# M661A.net
KiCad netlist of a schematic drawn in EAGLE
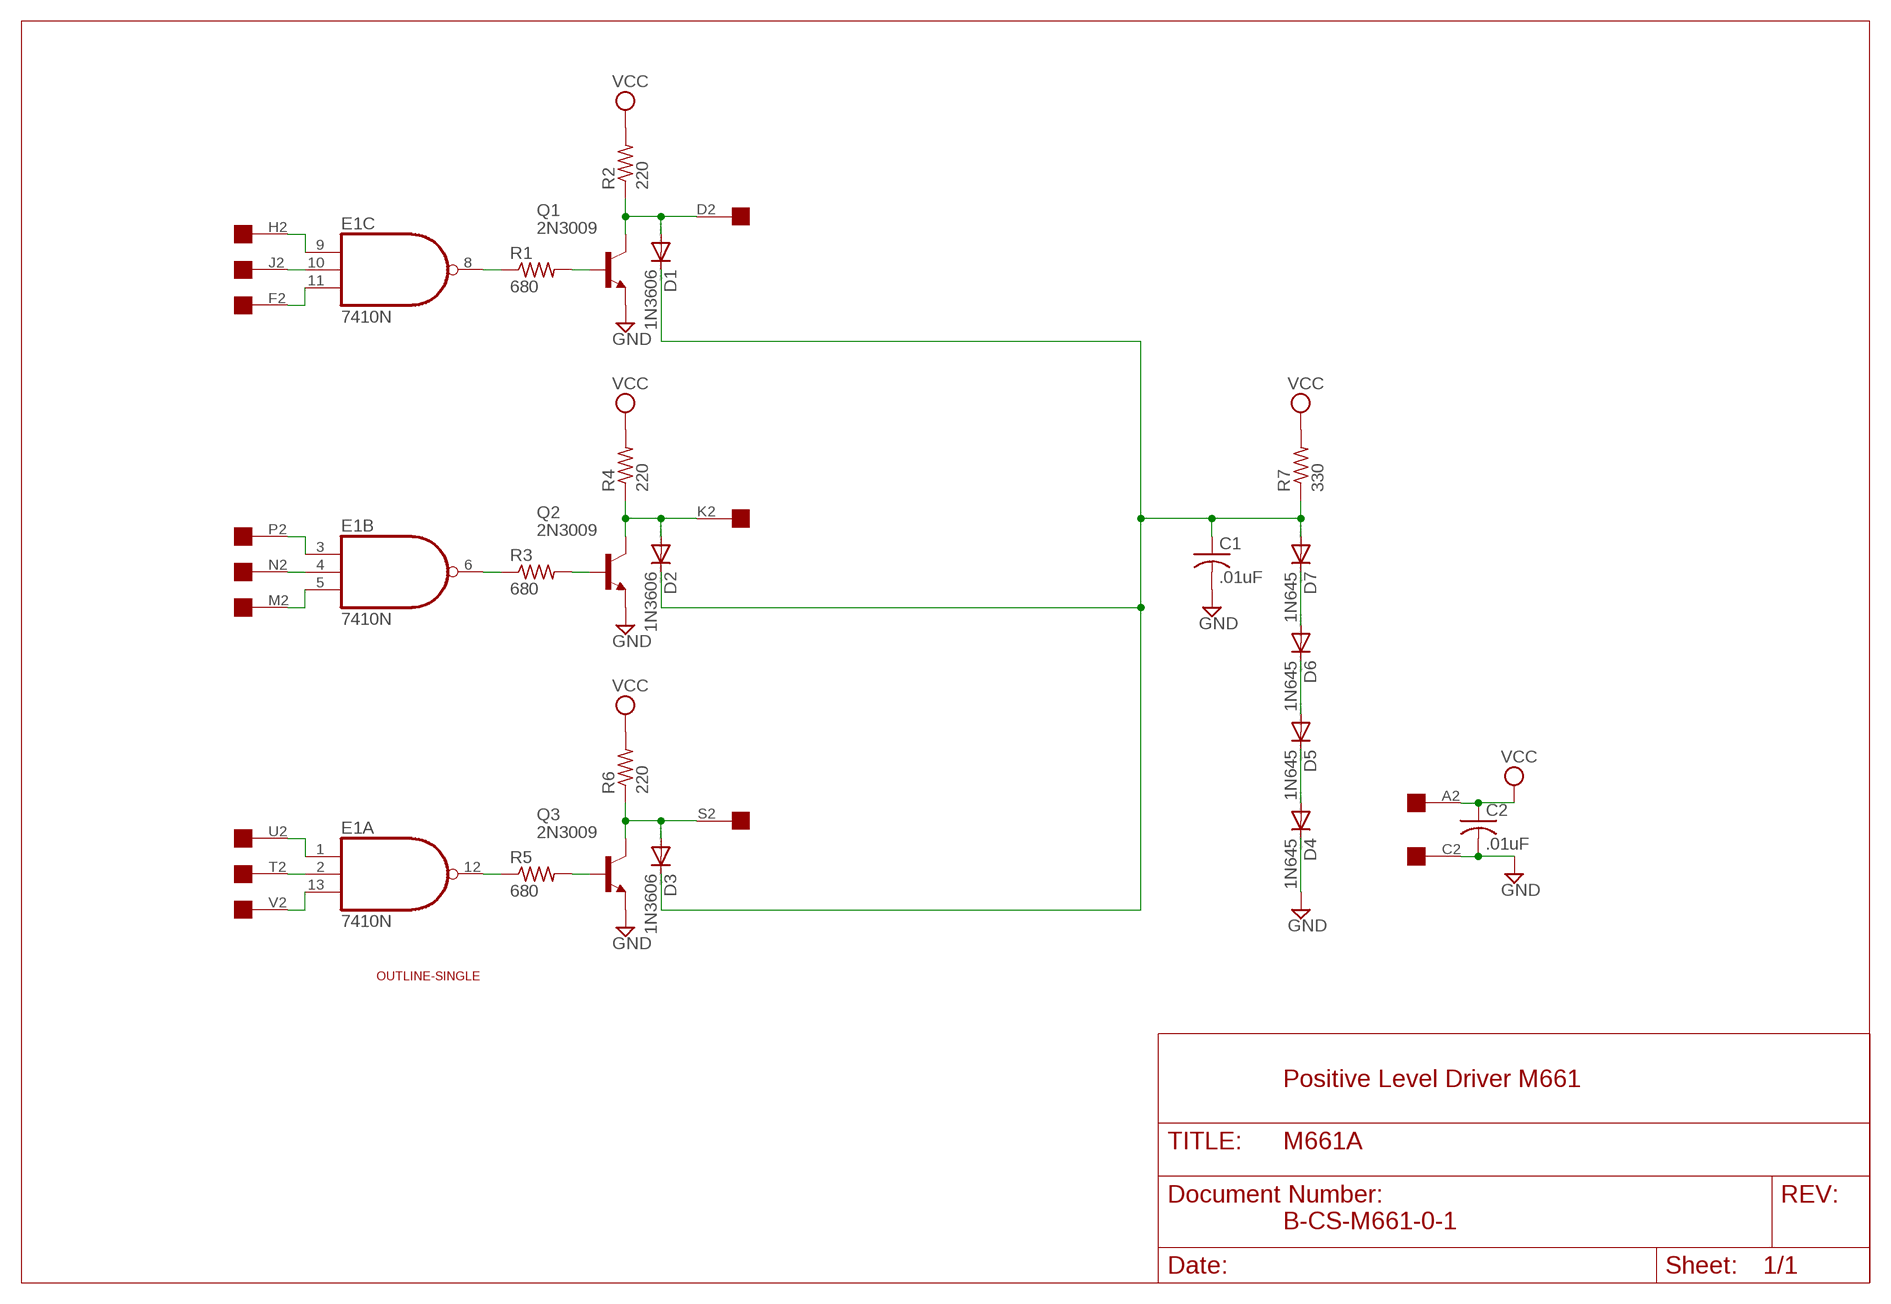
[diagram p0: schematic, sheet 1]

(export (version "E")
  (design (tool "Eeschema 10.0.6"))
  (components
    (comp (ref "C1")
      (value ".01uF")
      (footprint "eagle-import:C050-025X075")
      (libsource (lib "eagle-import") (part "C-US050-025X075"))
    )
    (comp (ref "C2")
      (value ".01uF")
      (footprint "eagle-import:C050-025X075")
      (libsource (lib "eagle-import") (part "C-US050-025X075"))
    )
    (comp (ref "D1")
      (value "1N3606")
      (footprint "eagle-import:DO35-10")
      (libsource (lib "eagle-import") (part "1N4148DO35-10"))
    )
    (comp (ref "D2")
      (value "1N3606")
      (footprint "eagle-import:DO35-10")
      (libsource (lib "eagle-import") (part "1N4148DO35-10"))
    )
    (comp (ref "D3")
      (value "1N3606")
      (footprint "eagle-import:DO35-10")
      (libsource (lib "eagle-import") (part "1N4148DO35-10"))
    )
    (comp (ref "D4")
      (value "1N645")
      (footprint "eagle-import:DO35-10")
      (libsource (lib "eagle-import") (part "1N4148DO35-10"))
    )
    (comp (ref "D5")
      (value "1N645")
      (footprint "eagle-import:DO35-10")
      (libsource (lib "eagle-import") (part "1N4148DO35-10"))
    )
    (comp (ref "D6")
      (value "1N645")
      (footprint "eagle-import:DO35-10")
      (libsource (lib "eagle-import") (part "1N4148DO35-10"))
    )
    (comp (ref "D7")
      (value "1N645")
      (footprint "eagle-import:DO35-10")
      (libsource (lib "eagle-import") (part "1N4148DO35-10"))
    )
    (comp (ref "E1")
      (value "7410N")
      (footprint "eagle-import:DIL14")
      (libsource (lib "eagle-import") (part "7410N"))
    )
    (comp (ref "Q1")
      (value "2N3009")
      (footprint "eagle-import:TO5")
      (libsource (lib "eagle-import") (part "2N2219"))
    )
    (comp (ref "Q2")
      (value "2N3009")
      (footprint "eagle-import:TO5")
      (libsource (lib "eagle-import") (part "2N2219"))
    )
    (comp (ref "Q3")
      (value "2N3009")
      (footprint "eagle-import:TO5")
      (libsource (lib "eagle-import") (part "2N2219"))
    )
    (comp (ref "R1")
      (value "680")
      (footprint "eagle-import:0207_10")
      (libsource (lib "eagle-import") (part "R-US_0207/10"))
    )
    (comp (ref "R2")
      (value "220")
      (footprint "eagle-import:0207_10")
      (libsource (lib "eagle-import") (part "R-US_0207/10"))
    )
    (comp (ref "R3")
      (value "680")
      (footprint "eagle-import:0207_10")
      (libsource (lib "eagle-import") (part "R-US_0207/10"))
    )
    (comp (ref "R4")
      (value "220")
      (footprint "eagle-import:0207_10")
      (libsource (lib "eagle-import") (part "R-US_0207/10"))
    )
    (comp (ref "R5")
      (value "680")
      (footprint "eagle-import:0207_10")
      (libsource (lib "eagle-import") (part "R-US_0207/10"))
    )
    (comp (ref "R6")
      (value "220")
      (footprint "eagle-import:0207_10")
      (libsource (lib "eagle-import") (part "R-US_0207/10"))
    )
    (comp (ref "R7")
      (value "330")
      (footprint "eagle-import:0207_10")
      (libsource (lib "eagle-import") (part "R-US_0207/10"))
    )
    (comp (ref "U$1")
      (value "OUTLINE-SINGLE")
      (footprint "eagle-import:SINGLE")
      (libsource (lib "eagle-import") (part "OUTLINE-SINGLE"))
    )
    (comp (ref "U$3")
      (value "EDGE-1")
      (footprint "eagle-import:EDGE-CON1")
      (libsource (lib "eagle-import") (part "EDGE-1"))
    )
  )
  (nets
    (net (code "1") (name "GND") (class "Default")
      (node (ref "C1") (pin "2") (pinfunction "2_2") (pintype "passive"))
      (node (ref "C2") (pin "2") (pinfunction "2_2") (pintype "passive"))
      (node (ref "D4") (pin "C") (pinfunction "C_C") (pintype "passive"))
      (node (ref "Q1") (pin "1") (pinfunction "E_1") (pintype "passive"))
      (node (ref "Q2") (pin "1") (pinfunction "E_1") (pintype "passive"))
      (node (ref "Q3") (pin "1") (pinfunction "E_1") (pintype "passive"))
      (node (ref "U$3") (pin "C2") (pinfunction "1_C2") (pintype "bidirectional"))
    )
    (net (code "2") (name "Net-(C1-Pad1)") (class "Default")
      (node (ref "C1") (pin "1") (pinfunction "1_1") (pintype "passive"))
      (node (ref "D1") (pin "C") (pinfunction "C_C") (pintype "passive"))
      (node (ref "D2") (pin "C") (pinfunction "C_C") (pintype "passive"))
      (node (ref "D3") (pin "C") (pinfunction "C_C") (pintype "passive"))
      (node (ref "D7") (pin "A") (pinfunction "A_A") (pintype "passive"))
      (node (ref "R7") (pin "1") (pinfunction "1_1") (pintype "passive"))
    )
    (net (code "3") (name "Net-(D4-PadA)") (class "Default")
      (node (ref "D4") (pin "A") (pinfunction "A_A") (pintype "passive"))
      (node (ref "D5") (pin "C") (pinfunction "C_C") (pintype "passive"))
    )
    (net (code "4") (name "Net-(D5-PadA)") (class "Default")
      (node (ref "D5") (pin "A") (pinfunction "A_A") (pintype "passive"))
      (node (ref "D6") (pin "C") (pinfunction "C_C") (pintype "passive"))
    )
    (net (code "5") (name "Net-(D6-PadA)") (class "Default")
      (node (ref "D6") (pin "A") (pinfunction "A_A") (pintype "passive"))
      (node (ref "D7") (pin "C") (pinfunction "C_C") (pintype "passive"))
    )
    (net (code "6") (name "Net-(E1A-I0)") (class "Default")
      (node (ref "E1") (pin "1") (pinfunction "I0_1") (pintype "input"))
      (node (ref "U$3") (pin "U2") (pinfunction "1_U2") (pintype "bidirectional"))
    )
    (net (code "7") (name "Net-(E1A-I1)") (class "Default")
      (node (ref "E1") (pin "2") (pinfunction "I1_2") (pintype "input"))
      (node (ref "U$3") (pin "T2") (pinfunction "1_T2") (pintype "bidirectional"))
    )
    (net (code "8") (name "Net-(E1A-I2)") (class "Default")
      (node (ref "E1") (pin "13") (pinfunction "I2_13") (pintype "input"))
      (node (ref "U$3") (pin "V2") (pinfunction "1_V2") (pintype "bidirectional"))
    )
    (net (code "9") (name "Net-(E1A-O)") (class "Default")
      (node (ref "E1") (pin "12") (pinfunction "O_12") (pintype "output"))
      (node (ref "R5") (pin "1") (pinfunction "1_1") (pintype "passive"))
    )
    (net (code "10") (name "Net-(E1B-I0)") (class "Default")
      (node (ref "E1") (pin "3") (pinfunction "I0_3") (pintype "input"))
      (node (ref "U$3") (pin "P2") (pinfunction "1_P2") (pintype "bidirectional"))
    )
    (net (code "11") (name "Net-(E1B-I1)") (class "Default")
      (node (ref "E1") (pin "4") (pinfunction "I1_4") (pintype "input"))
      (node (ref "U$3") (pin "N2") (pinfunction "1_N2") (pintype "bidirectional"))
    )
    (net (code "12") (name "Net-(E1B-I2)") (class "Default")
      (node (ref "E1") (pin "5") (pinfunction "I2_5") (pintype "input"))
      (node (ref "U$3") (pin "M2") (pinfunction "1_M2") (pintype "bidirectional"))
    )
    (net (code "13") (name "Net-(E1B-O)") (class "Default")
      (node (ref "E1") (pin "6") (pinfunction "O_6") (pintype "output"))
      (node (ref "R3") (pin "1") (pinfunction "1_1") (pintype "passive"))
    )
    (net (code "14") (name "Net-(E1C-I0)") (class "Default")
      (node (ref "E1") (pin "9") (pinfunction "I0_9") (pintype "input"))
      (node (ref "U$3") (pin "H2") (pinfunction "1_H2") (pintype "bidirectional"))
    )
    (net (code "15") (name "Net-(E1C-I1)") (class "Default")
      (node (ref "E1") (pin "10") (pinfunction "I1_10") (pintype "input"))
      (node (ref "U$3") (pin "J2") (pinfunction "1_J2") (pintype "bidirectional"))
    )
    (net (code "16") (name "Net-(E1C-I2)") (class "Default")
      (node (ref "E1") (pin "11") (pinfunction "I2_11") (pintype "input"))
      (node (ref "U$3") (pin "F2") (pinfunction "1_F2") (pintype "bidirectional"))
    )
    (net (code "17") (name "Net-(E1C-O)") (class "Default")
      (node (ref "E1") (pin "8") (pinfunction "O_8") (pintype "output"))
      (node (ref "R1") (pin "1") (pinfunction "1_1") (pintype "passive"))
    )
    (net (code "18") (name "Net-(Q1-B)") (class "Default")
      (node (ref "Q1") (pin "2") (pinfunction "B_2") (pintype "passive"))
      (node (ref "R1") (pin "2") (pinfunction "2_2") (pintype "passive"))
    )
    (net (code "19") (name "Net-(Q1-C)") (class "Default")
      (node (ref "D1") (pin "A") (pinfunction "A_A") (pintype "passive"))
      (node (ref "Q1") (pin "3") (pinfunction "C_3") (pintype "passive"))
      (node (ref "R2") (pin "1") (pinfunction "1_1") (pintype "passive"))
      (node (ref "U$3") (pin "D2") (pinfunction "1_D2") (pintype "bidirectional"))
    )
    (net (code "20") (name "Net-(Q2-B)") (class "Default")
      (node (ref "Q2") (pin "2") (pinfunction "B_2") (pintype "passive"))
      (node (ref "R3") (pin "2") (pinfunction "2_2") (pintype "passive"))
    )
    (net (code "21") (name "Net-(Q2-C)") (class "Default")
      (node (ref "D2") (pin "A") (pinfunction "A_A") (pintype "passive"))
      (node (ref "Q2") (pin "3") (pinfunction "C_3") (pintype "passive"))
      (node (ref "R4") (pin "1") (pinfunction "1_1") (pintype "passive"))
      (node (ref "U$3") (pin "K2") (pinfunction "1_K2") (pintype "bidirectional"))
    )
    (net (code "22") (name "Net-(Q3-B)") (class "Default")
      (node (ref "Q3") (pin "2") (pinfunction "B_2") (pintype "passive"))
      (node (ref "R5") (pin "2") (pinfunction "2_2") (pintype "passive"))
    )
    (net (code "23") (name "Net-(Q3-C)") (class "Default")
      (node (ref "D3") (pin "A") (pinfunction "A_A") (pintype "passive"))
      (node (ref "Q3") (pin "3") (pinfunction "C_3") (pintype "passive"))
      (node (ref "R6") (pin "1") (pinfunction "1_1") (pintype "passive"))
      (node (ref "U$3") (pin "S2") (pinfunction "1_S2") (pintype "bidirectional"))
    )
    (net (code "24") (name "VCC") (class "Default")
      (node (ref "C2") (pin "1") (pinfunction "1_1") (pintype "passive"))
      (node (ref "R2") (pin "2") (pinfunction "2_2") (pintype "passive"))
      (node (ref "R4") (pin "2") (pinfunction "2_2") (pintype "passive"))
      (node (ref "R6") (pin "2") (pinfunction "2_2") (pintype "passive"))
      (node (ref "R7") (pin "2") (pinfunction "2_2") (pintype "passive"))
      (node (ref "U$3") (pin "A2") (pinfunction "1_A2") (pintype "bidirectional"))
    )
  )
)
